# RobotArm.net
KiCad netlist of a schematic drawn in EAGLE
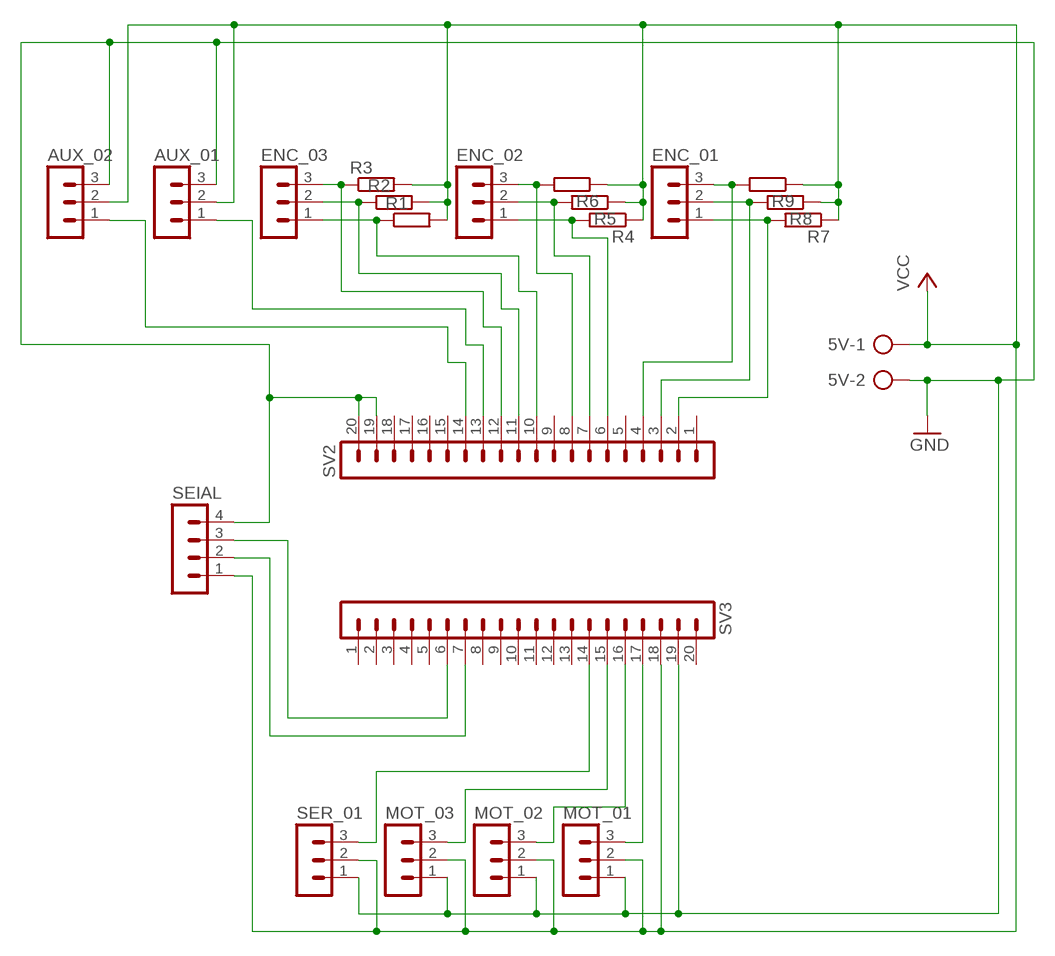
[diagram p0: schematic, sheet 1]

(export (version "E")
  (design (tool "Eeschema 10.0.6"))
  (components
    (comp (ref "5V")
      (value "AK500/2-H")
      (footprint "eagle-import:AK500_2-H")
      (libsource (lib "eagle-import") (part "AK500/2-H"))
    )
    (comp (ref "AUX_01")
      (value "MA03-1")
      (footprint "eagle-import:MA03-1")
      (libsource (lib "eagle-import") (part "MA03-1"))
    )
    (comp (ref "AUX_02")
      (value "MA03-1")
      (footprint "eagle-import:MA03-1")
      (libsource (lib "eagle-import") (part "MA03-1"))
    )
    (comp (ref "ENC_01")
      (value "MA03-1")
      (footprint "eagle-import:MA03-1")
      (libsource (lib "eagle-import") (part "MA03-1"))
    )
    (comp (ref "ENC_02")
      (value "MA03-1")
      (footprint "eagle-import:MA03-1")
      (libsource (lib "eagle-import") (part "MA03-1"))
    )
    (comp (ref "ENC_03")
      (value "MA03-1")
      (footprint "eagle-import:MA03-1")
      (libsource (lib "eagle-import") (part "MA03-1"))
    )
    (comp (ref "MOT_01")
      (value "MA03-1")
      (footprint "eagle-import:MA03-1")
      (libsource (lib "eagle-import") (part "MA03-1"))
    )
    (comp (ref "MOT_02")
      (value "MA03-1")
      (footprint "eagle-import:MA03-1")
      (libsource (lib "eagle-import") (part "MA03-1"))
    )
    (comp (ref "MOT_03")
      (value "MA03-1")
      (footprint "eagle-import:MA03-1")
      (libsource (lib "eagle-import") (part "MA03-1"))
    )
    (comp (ref "R1")
      (value "R-EU_0207/10")
      (footprint "eagle-import:0207_10")
      (libsource (lib "eagle-import") (part "R-EU_0207/10"))
    )
    (comp (ref "R2")
      (value "R-EU_0207/10")
      (footprint "eagle-import:0207_10")
      (libsource (lib "eagle-import") (part "R-EU_0207/10"))
    )
    (comp (ref "R3")
      (value "R-EU_0207/10")
      (footprint "eagle-import:0207_10")
      (libsource (lib "eagle-import") (part "R-EU_0207/10"))
    )
    (comp (ref "R4")
      (value "R-EU_0207/10")
      (footprint "eagle-import:0207_10")
      (libsource (lib "eagle-import") (part "R-EU_0207/10"))
    )
    (comp (ref "R5")
      (value "R-EU_0207/10")
      (footprint "eagle-import:0207_10")
      (libsource (lib "eagle-import") (part "R-EU_0207/10"))
    )
    (comp (ref "R6")
      (value "R-EU_0207/10")
      (footprint "eagle-import:0207_10")
      (libsource (lib "eagle-import") (part "R-EU_0207/10"))
    )
    (comp (ref "R7")
      (value "R-EU_0207/10")
      (footprint "eagle-import:0207_10")
      (libsource (lib "eagle-import") (part "R-EU_0207/10"))
    )
    (comp (ref "R8")
      (value "R-EU_0207/10")
      (footprint "eagle-import:0207_10")
      (libsource (lib "eagle-import") (part "R-EU_0207/10"))
    )
    (comp (ref "R9")
      (value "R-EU_0207/10")
      (footprint "eagle-import:0207_10")
      (libsource (lib "eagle-import") (part "R-EU_0207/10"))
    )
    (comp (ref "SEIAL")
      (value "MA04-1")
      (footprint "eagle-import:MA04-1")
      (libsource (lib "eagle-import") (part "MA04-1"))
    )
    (comp (ref "SER_01")
      (value "MA03-1")
      (footprint "eagle-import:MA03-1")
      (libsource (lib "eagle-import") (part "MA03-1"))
    )
    (comp (ref "SV2")
      (value "MA20-1")
      (footprint "eagle-import:MA20-1")
      (libsource (lib "eagle-import") (part "MA20-1"))
    )
    (comp (ref "SV3")
      (value "MA20-1")
      (footprint "eagle-import:MA20-1")
      (libsource (lib "eagle-import") (part "MA20-1"))
    )
  )
  (nets
    (net (code "1") (name "GND") (class "Default")
      (node (ref "5V") (pin "2") (pinfunction "KL_2") (pintype "passive"))
      (node (ref "AUX_01") (pin "3") (pinfunction "3_3") (pintype "passive"))
      (node (ref "AUX_02") (pin "3") (pinfunction "3_3") (pintype "passive"))
      (node (ref "MOT_01") (pin "1") (pinfunction "1_1") (pintype "passive"))
      (node (ref "MOT_02") (pin "1") (pinfunction "1_1") (pintype "passive"))
      (node (ref "MOT_03") (pin "1") (pinfunction "1_1") (pintype "passive"))
      (node (ref "SEIAL") (pin "4") (pinfunction "4_4") (pintype "passive"))
      (node (ref "SER_01") (pin "1") (pinfunction "1_1") (pintype "passive"))
      (node (ref "SV2") (pin "19") (pinfunction "19_19") (pintype "passive"))
      (node (ref "SV2") (pin "20") (pinfunction "20_20") (pintype "passive"))
      (node (ref "SV3") (pin "19") (pinfunction "19_19") (pintype "passive"))
    )
    (net (code "2") (name "Net-(AUX_01-Pad1)") (class "Default")
      (node (ref "AUX_01") (pin "1") (pinfunction "1_1") (pintype "passive"))
      (node (ref "SV2") (pin "13") (pinfunction "13_13") (pintype "passive"))
    )
    (net (code "3") (name "Net-(AUX_02-Pad1)") (class "Default")
      (node (ref "AUX_02") (pin "1") (pinfunction "1_1") (pintype "passive"))
      (node (ref "SV2") (pin "14") (pinfunction "14_14") (pintype "passive"))
    )
    (net (code "4") (name "Net-(ENC_01-Pad1)") (class "Default")
      (node (ref "ENC_01") (pin "1") (pinfunction "1_1") (pintype "passive"))
      (node (ref "R7") (pin "2") (pinfunction "2_2") (pintype "passive"))
      (node (ref "SV2") (pin "2") (pinfunction "2_2") (pintype "passive"))
    )
    (net (code "5") (name "Net-(ENC_01-Pad2)") (class "Default")
      (node (ref "ENC_01") (pin "2") (pinfunction "2_2") (pintype "passive"))
      (node (ref "R8") (pin "2") (pinfunction "2_2") (pintype "passive"))
      (node (ref "SV2") (pin "3") (pinfunction "3_3") (pintype "passive"))
    )
    (net (code "6") (name "Net-(ENC_01-Pad3)") (class "Default")
      (node (ref "ENC_01") (pin "3") (pinfunction "3_3") (pintype "passive"))
      (node (ref "R9") (pin "2") (pinfunction "2_2") (pintype "passive"))
      (node (ref "SV2") (pin "4") (pinfunction "4_4") (pintype "passive"))
    )
    (net (code "7") (name "Net-(ENC_02-Pad1)") (class "Default")
      (node (ref "ENC_02") (pin "1") (pinfunction "1_1") (pintype "passive"))
      (node (ref "R4") (pin "2") (pinfunction "2_2") (pintype "passive"))
      (node (ref "SV2") (pin "6") (pinfunction "6_6") (pintype "passive"))
    )
    (net (code "8") (name "Net-(ENC_02-Pad2)") (class "Default")
      (node (ref "ENC_02") (pin "2") (pinfunction "2_2") (pintype "passive"))
      (node (ref "R5") (pin "2") (pinfunction "2_2") (pintype "passive"))
      (node (ref "SV2") (pin "7") (pinfunction "7_7") (pintype "passive"))
    )
    (net (code "9") (name "Net-(ENC_02-Pad3)") (class "Default")
      (node (ref "ENC_02") (pin "3") (pinfunction "3_3") (pintype "passive"))
      (node (ref "R6") (pin "2") (pinfunction "2_2") (pintype "passive"))
      (node (ref "SV2") (pin "8") (pinfunction "8_8") (pintype "passive"))
    )
    (net (code "10") (name "Net-(ENC_03-Pad1)") (class "Default")
      (node (ref "ENC_03") (pin "1") (pinfunction "1_1") (pintype "passive"))
      (node (ref "R1") (pin "1") (pinfunction "1_1") (pintype "passive"))
      (node (ref "SV2") (pin "10") (pinfunction "10_10") (pintype "passive"))
    )
    (net (code "11") (name "Net-(ENC_03-Pad2)") (class "Default")
      (node (ref "ENC_03") (pin "2") (pinfunction "2_2") (pintype "passive"))
      (node (ref "R2") (pin "1") (pinfunction "1_1") (pintype "passive"))
      (node (ref "SV2") (pin "11") (pinfunction "11_11") (pintype "passive"))
    )
    (net (code "12") (name "Net-(ENC_03-Pad3)") (class "Default")
      (node (ref "ENC_03") (pin "3") (pinfunction "3_3") (pintype "passive"))
      (node (ref "R3") (pin "1") (pinfunction "1_1") (pintype "passive"))
      (node (ref "SV2") (pin "12") (pinfunction "12_12") (pintype "passive"))
    )
    (net (code "13") (name "Net-(MOT_01-Pad3)") (class "Default")
      (node (ref "MOT_01") (pin "3") (pinfunction "3_3") (pintype "passive"))
      (node (ref "SV3") (pin "17") (pinfunction "17_17") (pintype "passive"))
    )
    (net (code "14") (name "Net-(MOT_02-Pad3)") (class "Default")
      (node (ref "MOT_02") (pin "3") (pinfunction "3_3") (pintype "passive"))
      (node (ref "SV3") (pin "16") (pinfunction "16_16") (pintype "passive"))
    )
    (net (code "15") (name "Net-(MOT_03-Pad3)") (class "Default")
      (node (ref "MOT_03") (pin "3") (pinfunction "3_3") (pintype "passive"))
      (node (ref "SV3") (pin "15") (pinfunction "15_15") (pintype "passive"))
    )
    (net (code "16") (name "Net-(SEIAL-Pad2)") (class "Default")
      (node (ref "SEIAL") (pin "2") (pinfunction "2_2") (pintype "passive"))
      (node (ref "SV3") (pin "7") (pinfunction "7_7") (pintype "passive"))
    )
    (net (code "17") (name "Net-(SEIAL-Pad3)") (class "Default")
      (node (ref "SEIAL") (pin "3") (pinfunction "3_3") (pintype "passive"))
      (node (ref "SV3") (pin "6") (pinfunction "6_6") (pintype "passive"))
    )
    (net (code "18") (name "Net-(SER_01-Pad3)") (class "Default")
      (node (ref "SER_01") (pin "3") (pinfunction "3_3") (pintype "passive"))
      (node (ref "SV3") (pin "14") (pinfunction "14_14") (pintype "passive"))
    )
    (net (code "19") (name "VCC") (class "Default")
      (node (ref "5V") (pin "1") (pinfunction "KL_1") (pintype "passive"))
      (node (ref "AUX_01") (pin "2") (pinfunction "2_2") (pintype "passive"))
      (node (ref "AUX_02") (pin "2") (pinfunction "2_2") (pintype "passive"))
      (node (ref "MOT_01") (pin "2") (pinfunction "2_2") (pintype "passive"))
      (node (ref "MOT_02") (pin "2") (pinfunction "2_2") (pintype "passive"))
      (node (ref "MOT_03") (pin "2") (pinfunction "2_2") (pintype "passive"))
      (node (ref "R1") (pin "2") (pinfunction "2_2") (pintype "passive"))
      (node (ref "R2") (pin "2") (pinfunction "2_2") (pintype "passive"))
      (node (ref "R3") (pin "2") (pinfunction "2_2") (pintype "passive"))
      (node (ref "R4") (pin "1") (pinfunction "1_1") (pintype "passive"))
      (node (ref "R5") (pin "1") (pinfunction "1_1") (pintype "passive"))
      (node (ref "R6") (pin "1") (pinfunction "1_1") (pintype "passive"))
      (node (ref "R7") (pin "1") (pinfunction "1_1") (pintype "passive"))
      (node (ref "R8") (pin "1") (pinfunction "1_1") (pintype "passive"))
      (node (ref "R9") (pin "1") (pinfunction "1_1") (pintype "passive"))
      (node (ref "SEIAL") (pin "1") (pinfunction "1_1") (pintype "passive"))
      (node (ref "SER_01") (pin "2") (pinfunction "2_2") (pintype "passive"))
      (node (ref "SV3") (pin "18") (pinfunction "18_18") (pintype "passive"))
    )
    (net (code "20") (name "unconnected-(SV2-Pad1)") (class "Default")
      (node (ref "SV2") (pin "1") (pinfunction "1_1") (pintype "passive"))
    )
    (net (code "21") (name "unconnected-(SV2-Pad5)") (class "Default")
      (node (ref "SV2") (pin "5") (pinfunction "5_5") (pintype "passive"))
    )
    (net (code "22") (name "unconnected-(SV2-Pad9)") (class "Default")
      (node (ref "SV2") (pin "9") (pinfunction "9_9") (pintype "passive"))
    )
    (net (code "23") (name "unconnected-(SV2-Pad15)") (class "Default")
      (node (ref "SV2") (pin "15") (pinfunction "15_15") (pintype "passive"))
    )
    (net (code "24") (name "unconnected-(SV2-Pad16)") (class "Default")
      (node (ref "SV2") (pin "16") (pinfunction "16_16") (pintype "passive"))
    )
    (net (code "25") (name "unconnected-(SV2-Pad17)") (class "Default")
      (node (ref "SV2") (pin "17") (pinfunction "17_17") (pintype "passive"))
    )
    (net (code "26") (name "unconnected-(SV2-Pad18)") (class "Default")
      (node (ref "SV2") (pin "18") (pinfunction "18_18") (pintype "passive"))
    )
    (net (code "27") (name "unconnected-(SV3-Pad1)") (class "Default")
      (node (ref "SV3") (pin "1") (pinfunction "1_1") (pintype "passive"))
    )
    (net (code "28") (name "unconnected-(SV3-Pad2)") (class "Default")
      (node (ref "SV3") (pin "2") (pinfunction "2_2") (pintype "passive"))
    )
    (net (code "29") (name "unconnected-(SV3-Pad3)") (class "Default")
      (node (ref "SV3") (pin "3") (pinfunction "3_3") (pintype "passive"))
    )
    (net (code "30") (name "unconnected-(SV3-Pad4)") (class "Default")
      (node (ref "SV3") (pin "4") (pinfunction "4_4") (pintype "passive"))
    )
    (net (code "31") (name "unconnected-(SV3-Pad5)") (class "Default")
      (node (ref "SV3") (pin "5") (pinfunction "5_5") (pintype "passive"))
    )
    (net (code "32") (name "unconnected-(SV3-Pad8)") (class "Default")
      (node (ref "SV3") (pin "8") (pinfunction "8_8") (pintype "passive"))
    )
    (net (code "33") (name "unconnected-(SV3-Pad9)") (class "Default")
      (node (ref "SV3") (pin "9") (pinfunction "9_9") (pintype "passive"))
    )
    (net (code "34") (name "unconnected-(SV3-Pad10)") (class "Default")
      (node (ref "SV3") (pin "10") (pinfunction "10_10") (pintype "passive"))
    )
    (net (code "35") (name "unconnected-(SV3-Pad11)") (class "Default")
      (node (ref "SV3") (pin "11") (pinfunction "11_11") (pintype "passive"))
    )
    (net (code "36") (name "unconnected-(SV3-Pad12)") (class "Default")
      (node (ref "SV3") (pin "12") (pinfunction "12_12") (pintype "passive"))
    )
    (net (code "37") (name "unconnected-(SV3-Pad13)") (class "Default")
      (node (ref "SV3") (pin "13") (pinfunction "13_13") (pintype "passive"))
    )
    (net (code "38") (name "unconnected-(SV3-Pad20)") (class "Default")
      (node (ref "SV3") (pin "20") (pinfunction "20_20") (pintype "passive"))
    )
  )
)
